# BopITSCH.net
KiCad netlist of a schematic drawn in Altium Designer
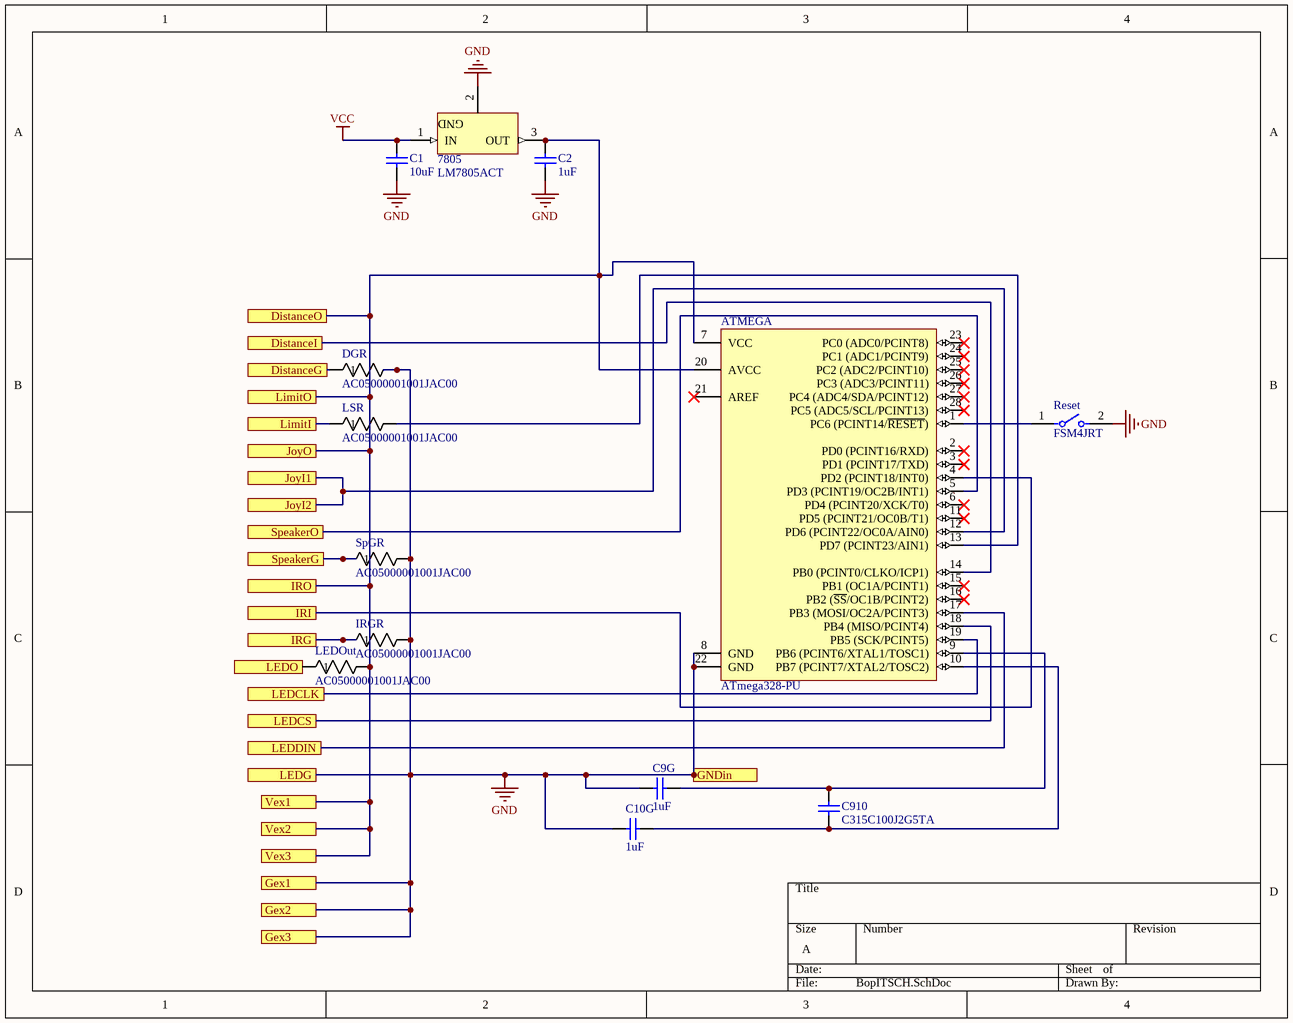
[diagram p0: BopITSCH.SchDoc]

(export (version "E")
  (design (tool "Eeschema 10.0.6"))
  (components
    (comp (ref "7805")
      (value "LM7805ACT")
      (footprint "FAIR-TO-220-3")
      (description "Positive Voltage Regulator, 5 V, 1 A, 0 to 125 degC, 3-Pin TO-220, RoHS, Tube")
      (fields (field (name "MANUFACTURER") "Fairchild"))
      (libsource (lib "Altium Content Vault") (part "FAIR-LM7805CT-TO220-3"))
    )
    (comp (ref "ATMEGA")
      (value "ATmega328-PU")
      (footprint "28P3")
      (libsource (lib "Altium Content Vault") (part "MC-8B-ATM48-IL28"))
    )
    (comp (ref "C1")
      (value "10uF")
      (footprint "KEMT-C315-THT-2")
      (description "Capacitor, Ceramic, 10 pF, +/-5 %, 200 V, 2-Pin THD, RoHS, Bulk")
      (libsource (lib "Altium Content Vault") (part "CAP-NP-2"))
    )
    (comp (ref "C2")
      (value "1uF")
      (footprint "KEMT-C315-THT-2")
      (description "Capacitor, Ceramic, 10 pF, +/-5 %, 200 V, 2-Pin THD, RoHS, Bulk")
      (libsource (lib "Altium Content Vault") (part "CAP-NP-2"))
    )
    (comp (ref "C9G")
      (value "1uF")
      (footprint "KEMT-C315-THT-2")
      (description "Capacitor, Ceramic, 10 pF, +/-5 %, 200 V, 2-Pin THD, RoHS, Bulk")
      (libsource (lib "Altium Content Vault") (part "CAP-NP-2"))
    )
    (comp (ref "C10G")
      (value "1uF")
      (footprint "KEMT-C315-THT-2")
      (description "Capacitor, Ceramic, 10 pF, +/-5 %, 200 V, 2-Pin THD, RoHS, Bulk")
      (libsource (lib "Altium Content Vault") (part "CAP-NP-2"))
    )
    (comp (ref "C910")
      (value "C315C100J2G5TA")
      (footprint "KEMT-C315-THT-2")
      (description "Capacitor, Ceramic, 10 pF, +/-5 %, 200 V, 2-Pin THD, RoHS, Bulk")
      (libsource (lib "Altium Content Vault") (part "CAP-NP-2"))
    )
    (comp (ref "DGR")
      (value "AC05000001001JAC00")
      (footprint "RES_AC05_VIS")
      (description "AC05000001001JAC00 Resistor, Wirewound, Res 1 Kilohms, Pwr-Rtg 5 W, Tol 5%, Axial, Ceramic Core")
      (fields (field (name "TOLERANCE") "5%"))
      (libsource (lib "Altium Content Vault") (part "AC05000001001JAC00"))
    )
    (comp (ref "IRGR")
      (value "AC05000001001JAC00")
      (footprint "RES_AC05_VIS")
      (description "AC05000001001JAC00 Resistor, Wirewound, Res 1 Kilohms, Pwr-Rtg 5 W, Tol 5%, Axial, Ceramic Core")
      (fields (field (name "TOLERANCE") "5%"))
      (libsource (lib "Altium Content Vault") (part "AC05000001001JAC00"))
    )
    (comp (ref "LEDOut")
      (value "AC05000001001JAC00")
      (footprint "RES_AC05_VIS")
      (description "AC05000001001JAC00 Resistor, Wirewound, Res 1 Kilohms, Pwr-Rtg 5 W, Tol 5%, Axial, Ceramic Core")
      (fields (field (name "TOLERANCE") "5%"))
      (libsource (lib "Altium Content Vault") (part "AC05000001001JAC00"))
    )
    (comp (ref "LSR")
      (value "AC05000001001JAC00")
      (footprint "RES_AC05_VIS")
      (description "AC05000001001JAC00 Resistor, Wirewound, Res 1 Kilohms, Pwr-Rtg 5 W, Tol 5%, Axial, Ceramic Core")
      (fields (field (name "TOLERANCE") "5%"))
      (libsource (lib "Altium Content Vault") (part "AC05000001001JAC00"))
    )
    (comp (ref "Reset")
      (value "FSM4JRT")
      (footprint "FP-FSM4JRT-MFG")
      (description "SWITCH TACTILE SPST-NO 0.05A 24V")
      (libsource (lib "Altium Content Vault") (part "bb27bde45df87f1f469753f287ef5ae"))
    )
    (comp (ref "SpGR")
      (value "AC05000001001JAC00")
      (footprint "RES_AC05_VIS")
      (description "AC05000001001JAC00 Resistor, Wirewound, Res 1 Kilohms, Pwr-Rtg 5 W, Tol 5%, Axial, Ceramic Core")
      (fields (field (name "TOLERANCE") "5%"))
      (libsource (lib "Altium Content Vault") (part "AC05000001001JAC00"))
    )
  )
  (nets
    (net (code "1") (name "/DistanceG") (class "Default")
      (node (ref "DGR") (pin "1") (pinfunction "1_1") (pintype "passive"))
    )
    (net (code "2") (name "/DistanceI") (class "Default")
      (node (ref "ATMEGA") (pin "14") (pinfunction "PB0_(PCINT0/CLKO/ICP1)_14") (pintype "bidirectional"))
    )
    (net (code "3") (name "/DistanceO") (class "Default")
      (node (ref "7805") (pin "3") (pinfunction "OUT_3") (pintype "output"))
      (node (ref "ATMEGA") (pin "20") (pinfunction "AVCC_20") (pintype "power_in"))
      (node (ref "ATMEGA") (pin "7") (pinfunction "VCC_7") (pintype "power_in"))
      (node (ref "C2") (pin "2") (pinfunction "2_2") (pintype "passive"))
      (node (ref "LEDOut") (pin "2") (pinfunction "2_2") (pintype "passive"))
    )
    (net (code "4") (name "/IRG") (class "Default")
      (node (ref "IRGR") (pin "1") (pinfunction "1_1") (pintype "passive"))
    )
    (net (code "5") (name "/IRI") (class "Default")
      (node (ref "ATMEGA") (pin "4") (pinfunction "PD2_(PCINT18/INT0)_4") (pintype "bidirectional"))
    )
    (net (code "6") (name "/JoyI1") (class "Default")
      (node (ref "ATMEGA") (pin "12") (pinfunction "PD6_(PCINT22/OC0A/AIN0)_12") (pintype "bidirectional"))
    )
    (net (code "7") (name "/LEDCLK") (class "Default")
      (node (ref "ATMEGA") (pin "19") (pinfunction "PB5_(SCK/PCINT5)_19") (pintype "bidirectional"))
    )
    (net (code "8") (name "/LEDCS") (class "Default")
      (node (ref "ATMEGA") (pin "18") (pinfunction "PB4_(MISO/PCINT4)_18") (pintype "bidirectional"))
    )
    (net (code "9") (name "/LEDDIN") (class "Default")
      (node (ref "ATMEGA") (pin "17") (pinfunction "PB3_(MOSI/OC2A/PCINT3)_17") (pintype "bidirectional"))
    )
    (net (code "10") (name "/LEDO") (class "Default")
      (node (ref "LEDOut") (pin "1") (pinfunction "1_1") (pintype "passive"))
    )
    (net (code "11") (name "/LimitI") (class "Default")
      (node (ref "LSR") (pin "1") (pinfunction "1_1") (pintype "passive"))
    )
    (net (code "12") (name "/SpeakerG") (class "Default")
      (node (ref "SpGR") (pin "1") (pinfunction "1_1") (pintype "passive"))
    )
    (net (code "13") (name "/SpeakerO") (class "Default")
      (node (ref "ATMEGA") (pin "5") (pinfunction "PD3_(PCINT19/OC2B/INT1)_5") (pintype "bidirectional"))
    )
    (net (code "14") (name "GND") (class "Default")
      (node (ref "7805") (pin "2") (pinfunction "GND_2") (pintype "power_in"))
      (node (ref "ATMEGA") (pin "22") (pinfunction "GND_22") (pintype "power_in"))
      (node (ref "ATMEGA") (pin "8") (pinfunction "GND_8") (pintype "power_in"))
      (node (ref "C1") (pin "1") (pinfunction "1_1") (pintype "passive"))
      (node (ref "C10G") (pin "2") (pinfunction "2_2") (pintype "passive"))
      (node (ref "C2") (pin "1") (pinfunction "1_1") (pintype "passive"))
      (node (ref "C9G") (pin "2") (pinfunction "2_2") (pintype "passive"))
      (node (ref "DGR") (pin "2") (pinfunction "2_2") (pintype "passive"))
      (node (ref "IRGR") (pin "2") (pinfunction "2_2") (pintype "passive"))
      (node (ref "Reset") (pin "2") (pinfunction "2_2") (pintype "passive"))
      (node (ref "SpGR") (pin "2") (pinfunction "2_2") (pintype "passive"))
    )
    (net (code "15") (name "Net-(ATMEGA-PB6_(PCINT6{slash}XTAL1{slash}TOSC1))") (class "Default")
      (node (ref "ATMEGA") (pin "9") (pinfunction "PB6_(PCINT6/XTAL1/TOSC1)_9") (pintype "bidirectional"))
      (node (ref "C910") (pin "2") (pinfunction "2_2") (pintype "passive"))
      (node (ref "C9G") (pin "1") (pinfunction "1_1") (pintype "passive"))
    )
    (net (code "16") (name "Net-(ATMEGA-PB7_(PCINT7{slash}XTAL2{slash}TOSC2))") (class "Default")
      (node (ref "ATMEGA") (pin "10") (pinfunction "PB7_(PCINT7/XTAL2/TOSC2)_10") (pintype "bidirectional"))
      (node (ref "C10G") (pin "1") (pinfunction "1_1") (pintype "passive"))
      (node (ref "C910") (pin "1") (pinfunction "1_1") (pintype "passive"))
    )
    (net (code "17") (name "Net-(ATMEGA-PC6_(PCINT14{slash}~{RESET}))") (class "Default")
      (node (ref "ATMEGA") (pin "1") (pinfunction "PC6_(PCINT14/~{RESET})_1") (pintype "bidirectional"))
      (node (ref "Reset") (pin "1") (pinfunction "1_1") (pintype "passive"))
    )
    (net (code "18") (name "Net-(ATMEGA-PD7_(PCINT23{slash}AIN1))") (class "Default")
      (node (ref "ATMEGA") (pin "13") (pinfunction "PD7_(PCINT23/AIN1)_13") (pintype "bidirectional"))
      (node (ref "LSR") (pin "2") (pinfunction "2_2") (pintype "passive"))
    )
    (net (code "19") (name "VCC") (class "Default")
      (node (ref "7805") (pin "1") (pinfunction "IN_1") (pintype "input"))
      (node (ref "C1") (pin "2") (pinfunction "2_2") (pintype "passive"))
    )
    (net (code "20") (name "unconnected-(ATMEGA-AREF-Pad21)") (class "Default")
      (node (ref "ATMEGA") (pin "21") (pinfunction "AREF_21") (pintype "power_in+no_connect"))
    )
    (net (code "21") (name "unconnected-(ATMEGA-PB1_(OC1A{slash}PCINT1)-Pad15)") (class "Default")
      (node (ref "ATMEGA") (pin "15") (pinfunction "PB1_(OC1A/PCINT1)_15") (pintype "bidirectional+no_connect"))
    )
    (net (code "22") (name "unconnected-(ATMEGA-PB2_(~{SS}{slash}OC1B{slash}PCINT2)-Pad16)") (class "Default")
      (node (ref "ATMEGA") (pin "16") (pinfunction "PB2_(~{SS}/OC1B/PCINT2)_16") (pintype "bidirectional+no_connect"))
    )
    (net (code "23") (name "unconnected-(ATMEGA-PC0_(ADC0{slash}PCINT8)-Pad23)") (class "Default")
      (node (ref "ATMEGA") (pin "23") (pinfunction "PC0_(ADC0/PCINT8)_23") (pintype "bidirectional+no_connect"))
    )
    (net (code "24") (name "unconnected-(ATMEGA-PC1_(ADC1{slash}PCINT9)-Pad24)") (class "Default")
      (node (ref "ATMEGA") (pin "24") (pinfunction "PC1_(ADC1/PCINT9)_24") (pintype "bidirectional+no_connect"))
    )
    (net (code "25") (name "unconnected-(ATMEGA-PC2_(ADC2{slash}PCINT10)-Pad25)") (class "Default")
      (node (ref "ATMEGA") (pin "25") (pinfunction "PC2_(ADC2/PCINT10)_25") (pintype "bidirectional+no_connect"))
    )
    (net (code "26") (name "unconnected-(ATMEGA-PC3_(ADC3{slash}PCINT11)-Pad26)") (class "Default")
      (node (ref "ATMEGA") (pin "26") (pinfunction "PC3_(ADC3/PCINT11)_26") (pintype "bidirectional+no_connect"))
    )
    (net (code "27") (name "unconnected-(ATMEGA-PC4_(ADC4{slash}SDA{slash}PCINT12)-Pad27)") (class "Default")
      (node (ref "ATMEGA") (pin "27") (pinfunction "PC4_(ADC4/SDA/PCINT12)_27") (pintype "bidirectional+no_connect"))
    )
    (net (code "28") (name "unconnected-(ATMEGA-PC5_(ADC5{slash}SCL{slash}PCINT13)-Pad28)") (class "Default")
      (node (ref "ATMEGA") (pin "28") (pinfunction "PC5_(ADC5/SCL/PCINT13)_28") (pintype "bidirectional+no_connect"))
    )
    (net (code "29") (name "unconnected-(ATMEGA-PD0_(PCINT16{slash}RXD)-Pad2)") (class "Default")
      (node (ref "ATMEGA") (pin "2") (pinfunction "PD0_(PCINT16/RXD)_2") (pintype "bidirectional+no_connect"))
    )
    (net (code "30") (name "unconnected-(ATMEGA-PD1_(PCINT17{slash}TXD)-Pad3)") (class "Default")
      (node (ref "ATMEGA") (pin "3") (pinfunction "PD1_(PCINT17/TXD)_3") (pintype "bidirectional+no_connect"))
    )
    (net (code "31") (name "unconnected-(ATMEGA-PD4_(PCINT20{slash}XCK{slash}T0)-Pad6)") (class "Default")
      (node (ref "ATMEGA") (pin "6") (pinfunction "PD4_(PCINT20/XCK/T0)_6") (pintype "bidirectional+no_connect"))
    )
    (net (code "32") (name "unconnected-(ATMEGA-PD5_(PCINT21{slash}OC0B{slash}T1)-Pad11)") (class "Default")
      (node (ref "ATMEGA") (pin "11") (pinfunction "PD5_(PCINT21/OC0B/T1)_11") (pintype "bidirectional+no_connect"))
    )
  )
)
